# main.net
KiCad netlist of a schematic drawn in Altium Designer
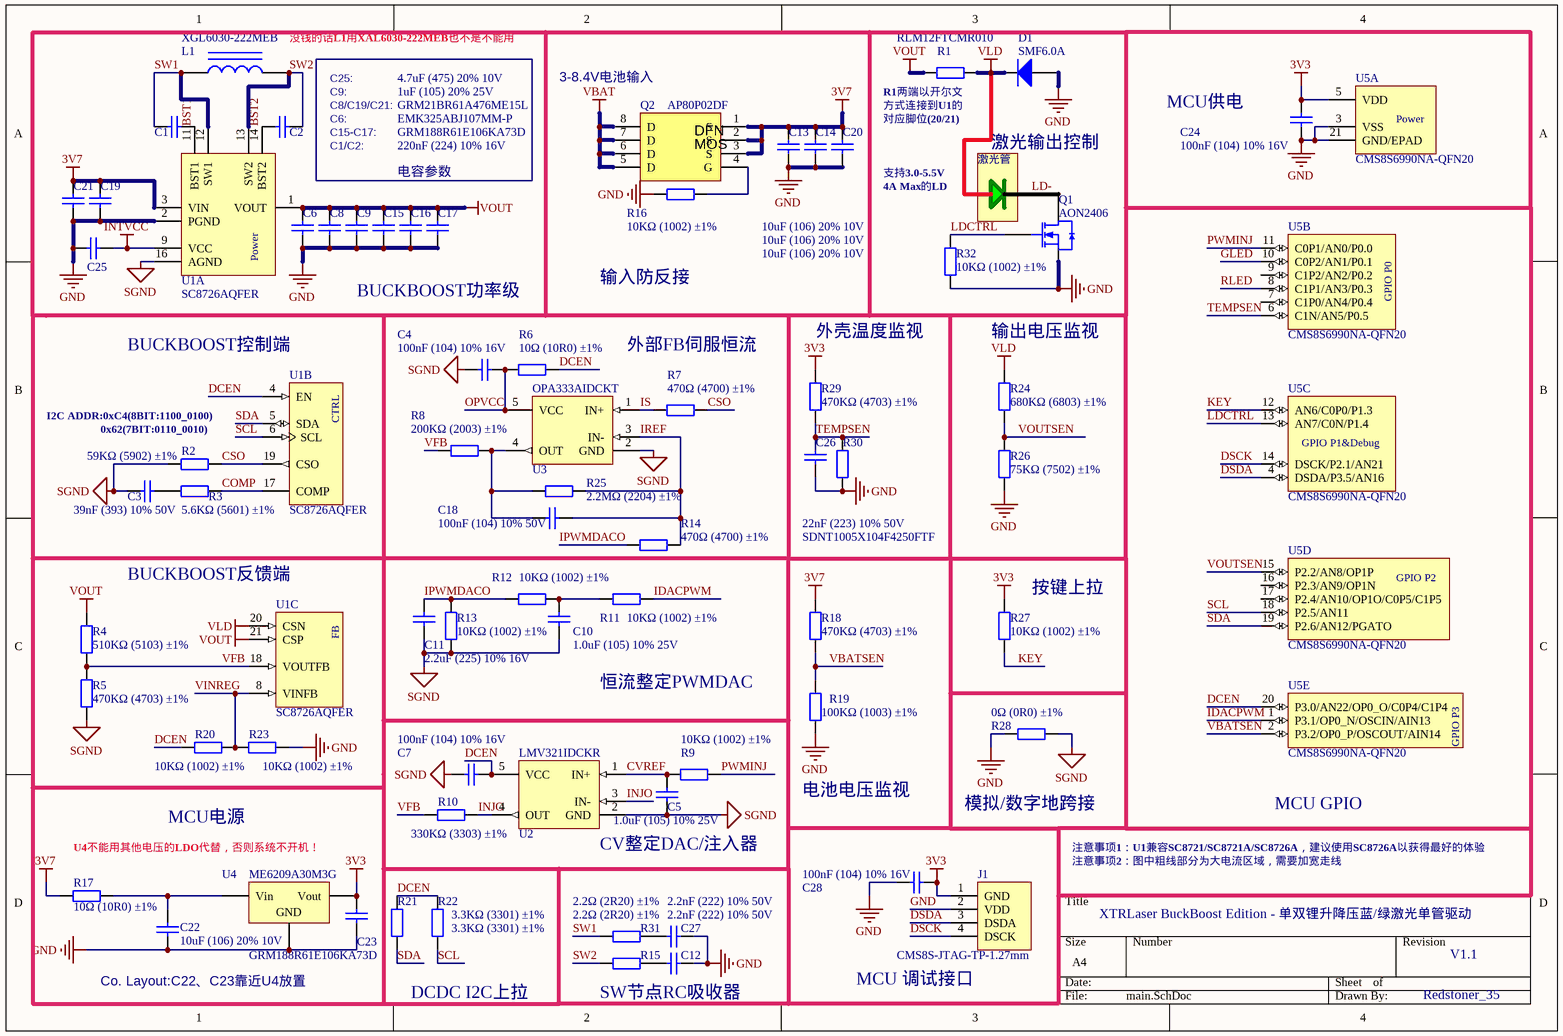
[diagram p0: main.SchDoc]

(export (version "E")
  (design (tool "Eeschema 10.0.6"))
  (components
    (comp (ref "C1")
      (value "220nF (224) 10% 16V")
      (footprint "0402_C")
      (description "贴片电容")
      (libsource (lib "Miscellaneous Devices LC") (part "0402 100nF (104) 10% 16V"))
    )
    (comp (ref "C2")
      (value "220nF (224) 10% 16V")
      (footprint "0402_C")
      (description "贴片电容")
      (libsource (lib "Miscellaneous Devices LC") (part "0402 100nF (104) 10% 16V"))
    )
    (comp (ref "C3")
      (value "39nF (393) 10% 50V")
      (footprint "0402_C")
      (description "贴片电容")
      (libsource (lib "Miscellaneous Devices LC") (part "0402 22nF (223) 10% 50V"))
    )
    (comp (ref "C4")
      (value "100nF (104) 10% 16V")
      (footprint "0402_C")
      (description "贴片电容")
      (libsource (lib "Miscellaneous Devices LC") (part "0402 100nF (104) 10% 16V"))
    )
    (comp (ref "C5")
      (value "1.0uF (105) 10% 25V")
      (footprint "0402_C")
      (description "贴片电容")
      (libsource (lib "Miscellaneous Devices LC") (part "0402 1.0uF (105) 10% 25V"))
    )
    (comp (ref "C6")
      (value "EMK325ABJ107MM-P")
      (footprint "1210C")
      (description "MLCC电容 10V 100uF±20% 16V X5R")
      (fields (field (name "PUBLISHER") "Altium Limited"))
      (libsource (lib "山猫的集成库20190318") (part "Cap"))
    )
    (comp (ref "C7")
      (value "100nF (104) 10% 16V")
      (footprint "0402_C")
      (description "贴片电容")
      (libsource (lib "Miscellaneous Devices LC") (part "0402 100nF (104) 10% 16V"))
    )
    (comp (ref "C8")
      (value "GRM21BR61A476ME15L")
      (footprint "0805_C")
      (description "贴片MLCC电容，47uF ±20% 10V X5R")
      (libsource (lib "Miscellaneous Devices LC") (part "0805 22uF (226) 20% 25V"))
    )
    (comp (ref "C9")
      (value "1uF (105) 20% 25V")
      (footprint "0402_C")
      (description "贴片电容")
      (libsource (lib "Miscellaneous Devices LC") (part "0402 4.7uF (475) 20% 10V"))
    )
    (comp (ref "C10")
      (value "1.0uF (105) 10% 25V")
      (footprint "0402_C")
      (description "贴片电容")
      (libsource (lib "Miscellaneous Devices LC") (part "0402 1.0uF (105) 10% 25V"))
    )
    (comp (ref "C11")
      (value "2.2uF (225) 10% 16V")
      (footprint "0402_C")
      (description "贴片电容")
      (libsource (lib "Miscellaneous Devices LC") (part "0402 2.2nF (222) 10% 50V"))
    )
    (comp (ref "C12")
      (value "2.2nF (222) 10% 50V")
      (footprint "0402_C")
      (description "贴片电容")
      (libsource (lib "Miscellaneous Devices LC") (part "0402 2.2nF (222) 10% 50V"))
    )
    (comp (ref "C13")
      (value "10uF (106) 20% 10V")
      (footprint "0402_C")
      (description "贴片电容")
      (libsource (lib "Miscellaneous Devices LC") (part "0402 10uF (106) 20% 6.3V"))
    )
    (comp (ref "C14")
      (value "10uF (106) 20% 10V")
      (footprint "0402_C")
      (description "贴片电容")
      (libsource (lib "Miscellaneous Devices LC") (part "0402 10uF (106) 20% 6.3V"))
    )
    (comp (ref "C15")
      (value "GRM188R61E106KA73D")
      (footprint "0603_C")
      (description "贴片MLCC电容 10uF±20% 10V X5R")
      (libsource (lib "Miscellaneous Devices LC") (part "0603 10uF (106) 10% 10V"))
    )
    (comp (ref "C16")
      (value "GRM188R61E106KA73D")
      (footprint "0603_C")
      (description "贴片MLCC电容 10uF±20% 10V X5R")
      (libsource (lib "Miscellaneous Devices LC") (part "0603 10uF (106) 10% 10V"))
    )
    (comp (ref "C17")
      (value "GRM188R61E106KA73D")
      (footprint "0603_C")
      (description "贴片MLCC电容 10uF±20% 10V X5R")
      (libsource (lib "Miscellaneous Devices LC") (part "0603 10uF (106) 10% 10V"))
    )
    (comp (ref "C18")
      (value "100nF (104) 10% 50V")
      (footprint "0402_C")
      (description "贴片电容")
      (libsource (lib "Miscellaneous Devices LC") (part "0402 10nF (103) 10% 50V"))
    )
    (comp (ref "C19")
      (value "GRM21BR61A476ME15L")
      (footprint "0805_C")
      (description "贴片MLCC电容，47uF ±20% 10V X5R")
      (libsource (lib "Miscellaneous Devices LC") (part "0805 22uF (226) 20% 25V"))
    )
    (comp (ref "C20")
      (value "10uF (106) 20% 10V")
      (footprint "0402_C")
      (description "贴片电容")
      (libsource (lib "Miscellaneous Devices LC") (part "0402 10uF (106) 20% 6.3V"))
    )
    (comp (ref "C21")
      (value "GRM21BR61A476ME15L")
      (footprint "0805_C")
      (description "贴片MLCC电容，47uF ±20% 10V X5R")
      (libsource (lib "Miscellaneous Devices LC") (part "0805 22uF (226) 20% 25V"))
    )
    (comp (ref "C22")
      (value "10uF (106) 20% 10V")
      (footprint "0402_C")
      (description "贴片电容")
      (libsource (lib "Miscellaneous Devices LC") (part "0402 10uF (106) 20% 6.3V"))
    )
    (comp (ref "C23")
      (value "GRM188R61E106KA73D")
      (footprint "0603_C")
      (description "贴片电容")
      (libsource (lib "Miscellaneous Devices LC") (part "0603 10uF (106) 10% 10V"))
    )
    (comp (ref "C24")
      (value "100nF (104) 10% 16V")
      (footprint "0402_C")
      (description "贴片电容")
      (libsource (lib "Miscellaneous Devices LC") (part "0402 100nF (104) 10% 16V"))
    )
    (comp (ref "C25")
      (value "4.7uF (475) 20% 10V")
      (footprint "0402_C")
      (description "贴片电容")
      (libsource (lib "Miscellaneous Devices LC") (part "0402 4.7uF (475) 20% 10V"))
    )
    (comp (ref "C26")
      (value "22nF (223) 10% 50V")
      (footprint "0402_C")
      (description "贴片电容")
      (libsource (lib "Miscellaneous Devices LC") (part "0402 10nF (103) 10% 50V"))
    )
    (comp (ref "C27")
      (value "2.2nF (222) 10% 50V")
      (footprint "0402_C")
      (description "贴片电容")
      (libsource (lib "Miscellaneous Devices LC") (part "0402 2.2nF (222) 10% 50V"))
    )
    (comp (ref "C28")
      (value "100nF (104) 10% 16V")
      (footprint "0402_C")
      (description "贴片电容")
      (libsource (lib "Miscellaneous Devices LC") (part "0402 100nF (104) 10% 16V"))
    )
    (comp (ref "D1")
      (value "SMF6.0A")
      (footprint "SOD-123")
      (description "TVS二极管 6V持续工作电压")
      (libsource (lib "Miscellaneous Devices LC") (part "SOD-123 B5819W  SL"))
    )
    (comp (ref "J1")
      (value "CMS8S-JTAG-TP-1.27mm")
      (footprint "CMS8S-JTAG-TP-2x2-P1.27")
      (description "面向CMS8S6990NA单片机的调试贴片触点，并不是元器件实物")
      (libsource (lib "custom") (part "CMS8S-JTAG-TP-1.27mm"))
    )
    (comp (ref "L1")
      (value "XGL6030-222MEB")
      (footprint "XAL6030-xxxME")
      (description "线艺XGL系列低损耗一体成型低内阻电感 2.2uH ±20% 8.7mΩ DCR 12A饱和电流")
      (fields (field (name "PUBLISHER") "Altium Limited"))
      (libsource (lib "Miscellaneous Devices") (part "Inductor Iron"))
    )
    (comp (ref "Q1")
      (value "AON2406")
      (footprint "PDFN-6_L2.0-W2.0-P0.65-BL-EP")
      (description "MOS(场效应管)")
      (libsource (lib "Miscellaneous Devices LC") (part "AO3400A N道沟 X0YV1T SOT-23"))
    )
    (comp (ref "Q2")
      (value "AP80P02DF")
      (footprint "DFN-8_L3.0-W3.0-P0.65-BL")
      (description "PDFN3x3 -20V 50A P沟道MOSFET 4.0mΩ @ -2.5V")
      (libsource (lib "custom") (part "SON/DFN5x6 MOS"))
    )
    (comp (ref "R1")
      (value "RLM12FTCMR010")
      (footprint "1206_R")
      (description "0.01Ω (R010) ±1% 1W 合金电流检测电阻")
      (libsource (lib "Miscellaneous Devices LC") (part "1206 0.1Ω (R100) 1%"))
    )
    (comp (ref "R2")
      (value "59KΩ (5902) ±1%")
      (footprint "0402_R")
      (description "贴片电阻")
      (libsource (lib "Miscellaneous Devices LC") (part "0402 56KΩ (5602) 1%"))
    )
    (comp (ref "R3")
      (value "5.6KΩ (5601) ±1%")
      (footprint "0402_R")
      (description "贴片电阻")
      (libsource (lib "Miscellaneous Devices LC") (part "0402 10KΩ (1002) 1%"))
    )
    (comp (ref "R4")
      (value "510KΩ (5103) ±1%")
      (footprint "0402_R")
      (description "贴片电阻")
      (libsource (lib "") (part "0402 100KΩ (1003) 1%_1"))
    )
    (comp (ref "R5")
      (value "470KΩ (4703) ±1%")
      (footprint "0402_R")
      (description "贴片电阻")
      (libsource (lib "") (part "0402 100KΩ (1003) 1%_1"))
    )
    (comp (ref "R6")
      (value "10Ω (10R0) ±1%")
      (footprint "0402_R")
      (description "贴片电阻")
      (libsource (lib "Miscellaneous Devices LC") (part "0402 10Ω (10R0) 1%"))
    )
    (comp (ref "R7")
      (value "470Ω (4700) ±1%")
      (footprint "0402_R")
      (description "贴片电阻")
      (libsource (lib "Miscellaneous Devices LC") (part "0402 470Ω (4700) 1%"))
    )
    (comp (ref "R8")
      (value "200KΩ (2003) ±1%")
      (footprint "0402_R")
      (description "贴片电阻")
      (libsource (lib "Miscellaneous Devices LC") (part "0402 100KΩ (1003) 1%"))
    )
    (comp (ref "R9")
      (value "10KΩ (1002) ±1%")
      (footprint "0402_R")
      (description "贴片电阻")
      (libsource (lib "Miscellaneous Devices LC") (part "0402 10KΩ (1002) 1%"))
    )
    (comp (ref "R10")
      (value "330KΩ (3303) ±1%")
      (footprint "0402_R")
      (description "贴片电阻")
      (libsource (lib "Miscellaneous Devices LC") (part "0402 330KΩ (3303) 1%"))
    )
    (comp (ref "R11")
      (value "10KΩ (1002) ±1%")
      (footprint "0402_R")
      (description "贴片电阻")
      (libsource (lib "Miscellaneous Devices LC") (part "0402 10KΩ (1002) 1%"))
    )
    (comp (ref "R12")
      (value "10KΩ (1002) ±1%")
      (footprint "0402_R")
      (description "贴片电阻")
      (libsource (lib "Miscellaneous Devices LC") (part "0402 10KΩ (1002) 1%"))
    )
    (comp (ref "R13")
      (value "10KΩ (1002) ±1%")
      (footprint "0402_R")
      (description "贴片电阻")
      (libsource (lib "") (part "0402 10KΩ (1002) 1%_2"))
    )
    (comp (ref "R14")
      (value "470Ω (4700) ±1%")
      (footprint "0402_R")
      (description "贴片电阻")
      (libsource (lib "") (part "0402 470Ω (4700) 1%_1"))
    )
    (comp (ref "R15")
      (value "2.2Ω (2R20) ±1%")
      (footprint "0402_R")
      (description "贴片电阻")
      (libsource (lib "") (part "0402 1Ω (1R00) 1%_1"))
    )
    (comp (ref "R16")
      (value "10KΩ (1002) ±1%")
      (footprint "0402_R")
      (description "贴片电阻")
      (libsource (lib "Miscellaneous Devices LC") (part "0402 10KΩ (1002) 1%"))
    )
    (comp (ref "R17")
      (value "10Ω (10R0) ±1%")
      (footprint "0402_R")
      (description "贴片电阻")
      (libsource (lib "Miscellaneous Devices LC") (part "0402 22Ω (22R0) 1%"))
    )
    (comp (ref "R18")
      (value "470KΩ (4703) ±1%")
      (footprint "0402_R")
      (description "贴片电阻")
      (libsource (lib "Miscellaneous Devices LC") (part "0402 470KΩ (4703) 1%"))
    )
    (comp (ref "R19")
      (value "100KΩ (1003) ±1%")
      (footprint "0402_R")
      (description "贴片电阻")
      (libsource (lib "") (part "0402 100KΩ (1003) 1%_1"))
    )
    (comp (ref "R20")
      (value "10KΩ (1002) ±1%")
      (footprint "0402_R")
      (description "贴片电阻")
      (libsource (lib "") (part "0402 10KΩ (1002) 1%_1"))
    )
    (comp (ref "R21")
      (value "3.3KΩ (3301) ±1%")
      (footprint "0402_R")
      (description "贴片电阻")
      (libsource (lib "Miscellaneous Devices LC") (part "0402 3.3KΩ (3301) 1%"))
    )
    (comp (ref "R22")
      (value "3.3KΩ (3301) ±1%")
      (footprint "0402_R")
      (description "贴片电阻")
      (libsource (lib "Miscellaneous Devices LC") (part "0402 3.3KΩ (3301) 1%"))
    )
    (comp (ref "R23")
      (value "10KΩ (1002) ±1%")
      (footprint "0402_R")
      (description "贴片电阻")
      (libsource (lib "") (part "0402 10KΩ (1002) 1%_1"))
    )
    (comp (ref "R24")
      (value "680KΩ (6803) ±1%")
      (footprint "0402_R")
      (description "贴片电阻")
      (libsource (lib "Miscellaneous Devices LC") (part "0402 470KΩ (4703) 1%"))
    )
    (comp (ref "R25")
      (value "2.2MΩ (2204) ±1%")
      (footprint "0402_R")
      (description "贴片电阻")
      (libsource (lib "Miscellaneous Devices LC") (part "0402 1MΩ (1004) 1%"))
    )
    (comp (ref "R26")
      (value "75KΩ (7502) ±1%")
      (footprint "0402_R")
      (description "贴片电阻")
      (libsource (lib "Miscellaneous Devices LC") (part "0402 68KΩ (6802) 1%"))
    )
    (comp (ref "R27")
      (value "10KΩ (1002) ±1%")
      (footprint "0402_R")
      (description "贴片电阻")
      (libsource (lib "") (part "0402 10KΩ (1002) 1%_2"))
    )
    (comp (ref "R28")
      (value "0Ω (0R0) ±1%")
      (footprint "0402_R")
      (description "贴片电阻")
      (libsource (lib "Miscellaneous Devices LC") (part "0402 0Ω (0R0) 1%"))
    )
    (comp (ref "R29")
      (value "470KΩ (4703) ±1%")
      (footprint "0402_R")
      (description "贴片电阻")
      (libsource (lib "Miscellaneous Devices LC") (part "0402 470KΩ (4703) 1%"))
    )
    (comp (ref "R30")
      (value "SDNT1005X104F4250FTF")
      (footprint "0402_R")
      (description "贴片热敏电阻0402 B4250 100K ±1%")
      (libsource (lib "Miscellaneous Devices LC") (part "0402 200KΩ (2003) 1%"))
    )
    (comp (ref "R31")
      (value "2.2Ω (2R20) ±1%")
      (footprint "0402_R")
      (description "贴片电阻")
      (libsource (lib "Miscellaneous Devices LC") (part "0402 1Ω (1R00) 1%"))
    )
    (comp (ref "R32")
      (value "10KΩ (1002) ±1%")
      (footprint "0402_R")
      (description "贴片电阻")
      (libsource (lib "") (part "0402 10KΩ (1002) 1%_2"))
    )
    (comp (ref "U1")
      (value "SC8726AQFER")
      (footprint "VQFN-21(4x4x0.75)")
      (description "同步单片集成式双向四开关单芯片集成升降压转换器，内置MOSFET，2.7-22V输入范围，2.4-22V输出范围，支持I2C控制")
      (libsource (lib "custom") (part "SC8721QFER"))
    )
    (comp (ref "U2")
      (value "LMV321IDCKR")
      (footprint "SC70-5")
      (description "CMOS超小型运算放大器，SC70-5")
      (libsource (lib "custom") (part "LMV321IDCKR"))
    )
    (comp (ref "U3")
      (value "OPA333AIDCKT")
      (footprint "SC70-5")
      (description "CMOS超小型0漂移运算放大器，SC70-5封装，350KHz GBW")
      (libsource (lib "custom") (part "LMV321IDCKR"))
    )
    (comp (ref "U4")
      (value "ME6209A30M3G")
      (footprint "SOT-23-3L")
      (description "低压差线性稳压(LDO)，输入耐压18V 输出3V 300mA最大电流 SOT23-3封装")
      (libsource (lib "Miscellaneous Devices LC") (part "SOT-23 XC6206P332MR"))
    )
    (comp (ref "U5")
      (value "CMS8S6990NA-QFN20")
      (footprint "QFN40P300X300X800_HS-21N")
      (description "增强型闪存1T 8051单片机，16KB Flash 256+1K XRAM")
      (libsource (lib "custom") (part "CM8S6990NA-QFN20"))
    )
  )
  (nets
    (net (code "1") (name "/BST1") (class "Default")
      (node (ref "C1") (pin "2") (pinfunction "2_2") (pintype "passive"))
      (node (ref "U1") (pin "11") (pinfunction "BST1_11") (pintype "power_in"))
    )
    (net (code "2") (name "/BST2") (class "Default")
      (node (ref "C2") (pin "1") (pinfunction "1_1") (pintype "passive"))
      (node (ref "U1") (pin "14") (pinfunction "BST2_14") (pintype "power_in"))
    )
    (net (code "3") (name "/COMP") (class "Default")
      (node (ref "R3") (pin "2") (pinfunction "2_2") (pintype "passive"))
      (node (ref "U1") (pin "17") (pinfunction "COMP_17") (pintype "passive"))
    )
    (net (code "4") (name "/CSO") (class "Default")
      (node (ref "R2") (pin "2") (pinfunction "2_2") (pintype "passive"))
      (node (ref "R7") (pin "2") (pinfunction "2_2") (pintype "passive"))
      (node (ref "U1") (pin "19") (pinfunction "CSO_19") (pintype "output"))
    )
    (net (code "5") (name "/CVREF") (class "Default")
      (node (ref "C5") (pin "2") (pinfunction "2_2") (pintype "passive"))
      (node (ref "R9") (pin "1") (pinfunction "1_1") (pintype "passive"))
      (node (ref "U2") (pin "1") (pinfunction "IN+_1") (pintype "input"))
    )
    (net (code "6") (name "/DCEN") (class "Default")
      (node (ref "C7") (pin "2") (pinfunction "2_2") (pintype "passive"))
      (node (ref "R20") (pin "2") (pinfunction "2_2") (pintype "passive"))
      (node (ref "R21") (pin "1") (pinfunction "1_1") (pintype "passive"))
      (node (ref "R22") (pin "1") (pinfunction "1_1") (pintype "passive"))
      (node (ref "R6") (pin "2") (pinfunction "2_2") (pintype "passive"))
      (node (ref "U1") (pin "4") (pinfunction "EN_4") (pintype "input"))
      (node (ref "U2") (pin "5") (pinfunction "VCC_5") (pintype "power_in"))
      (node (ref "U5") (pin "20") (pinfunction "P3.0/AN22/OP0_O/C0P4/C1P4_20") (pintype "bidirectional"))
    )
    (net (code "7") (name "/DSCK") (class "Default")
      (node (ref "J1") (pin "4") (pinfunction "DSCK_4") (pintype "passive"))
      (node (ref "U5") (pin "14") (pinfunction "DSCK/P2.1/AN21_14") (pintype "bidirectional"))
    )
    (net (code "8") (name "/DSDA") (class "Default")
      (node (ref "J1") (pin "3") (pinfunction "DSDA_3") (pintype "passive"))
      (node (ref "U5") (pin "4") (pinfunction "DSDA/P3.5/AN16_4") (pintype "bidirectional"))
    )
    (net (code "9") (name "/GLED") (class "Default")
      (node (ref "U5") (pin "10") (pinfunction "C0P2/AN1/P0.1_10") (pintype "bidirectional"))
    )
    (net (code "10") (name "/IDACPWM") (class "Default")
      (node (ref "R11") (pin "2") (pinfunction "2_2") (pintype "passive"))
      (node (ref "U5") (pin "1") (pinfunction "P3.1/OP0_N/OSCIN/AIN13_1") (pintype "bidirectional"))
    )
    (net (code "11") (name "/INJO") (class "Default")
      (node (ref "R10") (pin "2") (pinfunction "2_2") (pintype "passive"))
      (node (ref "U2") (pin "3") (pinfunction "IN-_3") (pintype "input"))
      (node (ref "U2") (pin "4") (pinfunction "OUT_4") (pintype "output"))
    )
    (net (code "12") (name "/IPWMDACO") (class "Default")
      (node (ref "C11") (pin "2") (pinfunction "2_2") (pintype "passive"))
      (node (ref "R12") (pin "1") (pinfunction "1_1") (pintype "passive"))
      (node (ref "R13") (pin "2") (pinfunction "2_2") (pintype "passive"))
      (node (ref "R14") (pin "2") (pinfunction "2_2") (pintype "passive"))
    )
    (net (code "13") (name "/IREF") (class "Default")
      (node (ref "C18") (pin "1") (pinfunction "1_1") (pintype "passive"))
      (node (ref "R14") (pin "1") (pinfunction "1_1") (pintype "passive"))
      (node (ref "R25") (pin "1") (pinfunction "1_1") (pintype "passive"))
      (node (ref "U3") (pin "3") (pinfunction "IN-_3") (pintype "input"))
    )
    (net (code "14") (name "/IS") (class "Default")
      (node (ref "R7") (pin "1") (pinfunction "1_1") (pintype "passive"))
      (node (ref "U3") (pin "1") (pinfunction "IN+_1") (pintype "input"))
    )
    (net (code "15") (name "/KEY") (class "Default")
      (node (ref "R27") (pin "1") (pinfunction "1_1") (pintype "passive"))
      (node (ref "U5") (pin "12") (pinfunction "AN6/C0P0/P1.3_12") (pintype "bidirectional"))
    )
    (net (code "16") (name "/LD-") (class "Default")
      (node (ref "Q1") (pin "3") (pinfunction "D_3") (pintype "passive"))
    )
    (net (code "17") (name "/LDCTRL") (class "Default")
      (node (ref "Q1") (pin "1") (pinfunction "G_1") (pintype "passive"))
      (node (ref "R32") (pin "2") (pinfunction "2_2") (pintype "passive"))
      (node (ref "U5") (pin "13") (pinfunction "AN7/C0N/P1.4_13") (pintype "bidirectional"))
    )
    (net (code "18") (name "/OPVCC") (class "Default")
      (node (ref "C4") (pin "2") (pinfunction "2_2") (pintype "passive"))
      (node (ref "R6") (pin "1") (pinfunction "1_1") (pintype "passive"))
      (node (ref "U3") (pin "5") (pinfunction "VCC_5") (pintype "power_in"))
    )
    (net (code "19") (name "/PWMINJ") (class "Default")
      (node (ref "R9") (pin "2") (pinfunction "2_2") (pintype "passive"))
      (node (ref "U5") (pin "11") (pinfunction "C0P1/AN0/P0.0_11") (pintype "bidirectional"))
    )
    (net (code "20") (name "/RLED") (class "Default")
      (node (ref "U5") (pin "8") (pinfunction "C1P1/AN3/P0.3_8") (pintype "bidirectional"))
    )
    (net (code "21") (name "/SCL") (class "Default")
      (node (ref "R22") (pin "2") (pinfunction "2_2") (pintype "passive"))
      (node (ref "U1") (pin "6") (pinfunction "SCL_6") (pintype "input"))
      (node (ref "U5") (pin "18") (pinfunction "P2.5/AN11_18") (pintype "bidirectional"))
    )
    (net (code "22") (name "/SDA") (class "Default")
      (node (ref "R21") (pin "2") (pinfunction "2_2") (pintype "passive"))
      (node (ref "U1") (pin "5") (pinfunction "SDA_5") (pintype "bidirectional"))
      (node (ref "U5") (pin "19") (pinfunction "P2.6/AN12/PGATO_19") (pintype "bidirectional"))
    )
    (net (code "23") (name "/SW1") (class "Default")
      (node (ref "C1") (pin "1") (pinfunction "1_1") (pintype "passive"))
      (node (ref "L1") (pin "1") (pinfunction "1_1") (pintype "passive"))
      (node (ref "R31") (pin "2") (pinfunction "2_2") (pintype "passive"))
      (node (ref "U1") (pin "12") (pinfunction "SW1_12") (pintype "power_in"))
    )
    (net (code "24") (name "/SW2") (class "Default")
      (node (ref "C2") (pin "2") (pinfunction "2_2") (pintype "passive"))
      (node (ref "L1") (pin "2") (pinfunction "2_2") (pintype "passive"))
      (node (ref "R15") (pin "1") (pinfunction "1_1") (pintype "passive"))
      (node (ref "U1") (pin "13") (pinfunction "SW2_13") (pintype "power_in"))
    )
    (net (code "25") (name "/TEMPSEN") (class "Default")
      (node (ref "C26") (pin "2") (pinfunction "2_2") (pintype "passive"))
      (node (ref "R29") (pin "1") (pinfunction "1_1") (pintype "passive"))
      (node (ref "R30") (pin "2") (pinfunction "2_2") (pintype "passive"))
      (node (ref "U5") (pin "6") (pinfunction "C1N/AN5/P0.5_6") (pintype "bidirectional"))
    )
    (net (code "26") (name "/VBATSEN") (class "Default")
      (node (ref "R18") (pin "1") (pinfunction "1_1") (pintype "passive"))
      (node (ref "R19") (pin "2") (pinfunction "2_2") (pintype "passive"))
      (node (ref "U5") (pin "2") (pinfunction "P3.2/OP0_P/OSCOUT/AIN14_2") (pintype "bidirectional"))
    )
    (net (code "27") (name "/VFB") (class "Default")
      (node (ref "R10") (pin "1") (pinfunction "1_1") (pintype "passive"))
      (node (ref "R4") (pin "1") (pinfunction "1_1") (pintype "passive"))
      (node (ref "R5") (pin "2") (pinfunction "2_2") (pintype "passive"))
      (node (ref "R8") (pin "1") (pinfunction "1_1") (pintype "passive"))
      (node (ref "U1") (pin "18") (pinfunction "VOUTFB_18") (pintype "input"))
    )
    (net (code "28") (name "/VINREG") (class "Default")
      (node (ref "R20") (pin "1") (pinfunction "1_1") (pintype "passive"))
      (node (ref "R23") (pin "2") (pinfunction "2_2") (pintype "passive"))
      (node (ref "U1") (pin "8") (pinfunction "VINFB_8") (pintype "input"))
    )
    (net (code "29") (name "/VOUTSEN") (class "Default")
      (node (ref "R24") (pin "1") (pinfunction "1_1") (pintype "passive"))
      (node (ref "R26") (pin "2") (pinfunction "2_2") (pintype "passive"))
      (node (ref "U5") (pin "15") (pinfunction "P2.2/AN8/OP1P_15") (pintype "bidirectional"))
    )
    (net (code "30") (name "3V3") (class "Default")
      (node (ref "C23") (pin "2") (pinfunction "2_2") (pintype "passive"))
      (node (ref "C24") (pin "2") (pinfunction "2_2") (pintype "passive"))
      (node (ref "C28") (pin "1") (pinfunction "1_1") (pintype "passive"))
      (node (ref "J1") (pin "1") (pinfunction "GND_1") (pintype "passive"))
      (node (ref "R27") (pin "2") (pinfunction "2_2") (pintype "passive"))
      (node (ref "R29") (pin "2") (pinfunction "2_2") (pintype "passive"))
      (node (ref "U4") (pin "2") (pinfunction "Vout_2") (pintype "passive"))
      (node (ref "U5") (pin "5") (pinfunction "VDD_5") (pintype "power_in"))
    )
    (net (code "31") (name "3V7") (class "Default")
      (node (ref "C13") (pin "2") (pinfunction "2_2") (pintype "passive"))
      (node (ref "C14") (pin "2") (pinfunction "2_2") (pintype "passive"))
      (node (ref "C19") (pin "2") (pinfunction "2_2") (pintype "passive"))
      (node (ref "C20") (pin "2") (pinfunction "2_2") (pintype "passive"))
      (node (ref "C21") (pin "2") (pinfunction "2_2") (pintype "passive"))
      (node (ref "Q2") (pin "1") (pinfunction "S_1") (pintype "passive"))
      (node (ref "Q2") (pin "2") (pinfunction "S_2") (pintype "passive"))
      (node (ref "Q2") (pin "3") (pinfunction "S_3") (pintype "passive"))
      (node (ref "R17") (pin "1") (pinfunction "1_1") (pintype "passive"))
      (node (ref "R18") (pin "2") (pinfunction "2_2") (pintype "passive"))
      (node (ref "U1") (pin "3") (pinfunction "VIN_3") (pintype "power_in"))
    )
    (net (code "32") (name "GND") (class "Default")
      (node (ref "C12") (pin "2") (pinfunction "2_2") (pintype "passive"))
      (node (ref "C13") (pin "1") (pinfunction "1_1") (pintype "passive"))
      (node (ref "C14") (pin "1") (pinfunction "1_1") (pintype "passive"))
      (node (ref "C15") (pin "1") (pinfunction "1_1") (pintype "passive"))
      (node (ref "C16") (pin "1") (pinfunction "1_1") (pintype "passive"))
      (node (ref "C17") (pin "1") (pinfunction "1_1") (pintype "passive"))
      (node (ref "C19") (pin "1") (pinfunction "1_1") (pintype "passive"))
      (node (ref "C20") (pin "1") (pinfunction "1_1") (pintype "passive"))
      (node (ref "C21") (pin "1") (pinfunction "1_1") (pintype "passive"))
      (node (ref "C22") (pin "1") (pinfunction "1_1") (pintype "passive"))
      (node (ref "C23") (pin "1") (pinfunction "1_1") (pintype "passive"))
      (node (ref "C24") (pin "1") (pinfunction "1_1") (pintype "passive"))
      (node (ref "C25") (pin "1") (pinfunction "1_1") (pintype "passive"))
      (node (ref "C26") (pin "1") (pinfunction "1_1") (pintype "passive"))
      (node (ref "C27") (pin "1") (pinfunction "1_1") (pintype "passive"))
      (node (ref "C28") (pin "2") (pinfunction "2_2") (pintype "passive"))
      (node (ref "C6") (pin "1") (pinfunction "1_1") (pintype "passive"))
      (node (ref "C8") (pin "1") (pinfunction "1_1") (pintype "passive"))
      (node (ref "C9") (pin "2") (pinfunction "2_2") (pintype "passive"))
      (node (ref "D1") (pin "1") (pinfunction "A_1") (pintype "passive"))
      (node (ref "J1") (pin "2") (pinfunction "VDD_2") (pintype "passive"))
      (node (ref "Q1") (pin "2") (pinfunction "S_2") (pintype "passive"))
      (node (ref "R16") (pin "1") (pinfunction "1_1") (pintype "passive"))
      (node (ref "R19") (pin "1") (pinfunction "1_1") (pintype "passive"))
      (node (ref "R23") (pin "1") (pinfunction "1_1") (pintype "passive"))
      (node (ref "R26") (pin "1") (pinfunction "1_1") (pintype "passive"))
      (node (ref "R28") (pin "2") (pinfunction "2_2") (pintype "passive"))
      (node (ref "R30") (pin "1") (pinfunction "1_1") (pintype "passive"))
      (node (ref "R32") (pin "1") (pinfunction "1_1") (pintype "passive"))
      (node (ref "U1") (pin "2") (pinfunction "PGND_2") (pintype "power_in"))
      (node (ref "U4") (pin "1") (pinfunction "GND_1") (pintype "passive"))
      (node (ref "U5") (pin "21") (pinfunction "GND/EPAD_21") (pintype "power_in"))
      (node (ref "U5") (pin "3") (pinfunction "VSS_3") (pintype "power_in"))
    )
    (net (code "33") (name "INTVCC") (class "Default")
      (node (ref "C25") (pin "2") (pinfunction "2_2") (pintype "passive"))
      (node (ref "U1") (pin "9") (pinfunction "VCC_9") (pintype "power_in"))
    )
    (net (code "34") (name "Net-(C3-Pad2)") (class "Default")
      (node (ref "C3") (pin "2") (pinfunction "2_2") (pintype "passive"))
      (node (ref "R3") (pin "1") (pinfunction "1_1") (pintype "passive"))
    )
    (net (code "35") (name "Net-(C10-Pad1)") (class "Default")
      (node (ref "C10") (pin "1") (pinfunction "1_1") (pintype "passive"))
      (node (ref "R11") (pin "1") (pinfunction "1_1") (pintype "passive"))
      (node (ref "R12") (pin "2") (pinfunction "2_2") (pintype "passive"))
    )
    (net (code "36") (name "Net-(C12-Pad1)") (class "Default")
      (node (ref "C12") (pin "1") (pinfunction "1_1") (pintype "passive"))
      (node (ref "R15") (pin "2") (pinfunction "2_2") (pintype "passive"))
    )
    (net (code "37") (name "Net-(C27-Pad2)") (class "Default")
      (node (ref "C27") (pin "2") (pinfunction "2_2") (pintype "passive"))
      (node (ref "R31") (pin "1") (pinfunction "1_1") (pintype "passive"))
    )
    (net (code "38") (name "Net-(Q2-G)") (class "Default")
      (node (ref "Q2") (pin "4") (pinfunction "G_4") (pintype "passive"))
      (node (ref "R16") (pin "2") (pinfunction "2_2") (pintype "passive"))
    )
    (net (code "39") (name "Net-(U3-OUT)") (class "Default")
      (node (ref "C18") (pin "2") (pinfunction "2_2") (pintype "passive"))
      (node (ref "R25") (pin "2") (pinfunction "2_2") (pintype "passive"))
      (node (ref "R8") (pin "2") (pinfunction "2_2") (pintype "passive"))
      (node (ref "U3") (pin "4") (pinfunction "OUT_4") (pintype "output"))
    )
    (net (code "40") (name "Net-(U4-Vin)") (class "Default")
      (node (ref "C22") (pin "2") (pinfunction "2_2") (pintype "passive"))
      (node (ref "R17") (pin "2") (pinfunction "2_2") (pintype "passive"))
      (node (ref "U4") (pin "3") (pinfunction "Vin_3") (pintype "passive"))
    )
    (net (code "41") (name "SGND") (class "Default")
      (node (ref "C10") (pin "2") (pinfunction "2_2") (pintype "passive"))
      (node (ref "C11") (pin "1") (pinfunction "1_1") (pintype "passive"))
      (node (ref "C3") (pin "1") (pinfunction "1_1") (pintype "passive"))
      (node (ref "C4") (pin "1") (pinfunction "1_1") (pintype "passive"))
      (node (ref "C5") (pin "1") (pinfunction "1_1") (pintype "passive"))
      (node (ref "C7") (pin "1") (pinfunction "1_1") (pintype "passive"))
      (node (ref "R13") (pin "1") (pinfunction "1_1") (pintype "passive"))
      (node (ref "R2") (pin "1") (pinfunction "1_1") (pintype "passive"))
      (node (ref "R28") (pin "1") (pinfunction "1_1") (pintype "passive"))
      (node (ref "R5") (pin "1") (pinfunction "1_1") (pintype "passive"))
      (node (ref "U1") (pin "16") (pinfunction "AGND_16") (pintype "power_in"))
      (node (ref "U2") (pin "2") (pinfunction "GND_2") (pintype "power_in"))
      (node (ref "U3") (pin "2") (pinfunction "GND_2") (pintype "power_in"))
    )
    (net (code "42") (name "VBAT") (class "Default")
      (node (ref "Q2") (pin "5") (pinfunction "D_5") (pintype "passive"))
      (node (ref "Q2") (pin "6") (pinfunction "D_6") (pintype "passive"))
      (node (ref "Q2") (pin "7") (pinfunction "D_7") (pintype "passive"))
      (node (ref "Q2") (pin "8") (pinfunction "D_8") (pintype "passive"))
    )
    (net (code "43") (name "VLD") (class "Default")
      (node (ref "D1") (pin "2") (pinfunction "K_2") (pintype "passive"))
      (node (ref "R1") (pin "2") (pinfunction "2_2") (pintype "passive"))
      (node (ref "R24") (pin "2") (pinfunction "2_2") (pintype "passive"))
      (node (ref "U1") (pin "20") (pinfunction "CSN_20") (pintype "input"))
    )
    (net (code "44") (name "VOUT") (class "Default")
      (node (ref "C15") (pin "2") (pinfunction "2_2") (pintype "passive"))
      (node (ref "C16") (pin "2") (pinfunction "2_2") (pintype "passive"))
      (node (ref "C17") (pin "2") (pinfunction "2_2") (pintype "passive"))
      (node (ref "C6") (pin "2") (pinfunction "2_2") (pintype "passive"))
      (node (ref "C8") (pin "2") (pinfunction "2_2") (pintype "passive"))
      (node (ref "C9") (pin "1") (pinfunction "1_1") (pintype "passive"))
      (node (ref "R1") (pin "1") (pinfunction "1_1") (pintype "passive"))
      (node (ref "R4") (pin "2") (pinfunction "2_2") (pintype "passive"))
      (node (ref "U1") (pin "1") (pinfunction "VOUT_1") (pintype "power_in"))
      (node (ref "U1") (pin "21") (pinfunction "CSP_21") (pintype "input"))
    )
    (net (code "45") (name "unconnected-(U5B-C1P0{slash}AN4{slash}P0.4-Pad7)") (class "Default")
      (node (ref "U5") (pin "7") (pinfunction "C1P0/AN4/P0.4_7") (pintype "bidirectional"))
    )
    (net (code "46") (name "unconnected-(U5B-C1P2{slash}AN2{slash}P0.2-Pad9)") (class "Default")
      (node (ref "U5") (pin "9") (pinfunction "C1P2/AN2/P0.2_9") (pintype "bidirectional"))
    )
    (net (code "47") (name "unconnected-(U5D-P2.3{slash}AN9{slash}OP1N-Pad16)") (class "Default")
      (node (ref "U5") (pin "16") (pinfunction "P2.3/AN9/OP1N_16") (pintype "bidirectional"))
    )
    (net (code "48") (name "unconnected-(U5D-P2.4{slash}AN10{slash}OP1O{slash}C0P5{slash}C1P5-Pad17)") (class "Default")
      (node (ref "U5") (pin "17") (pinfunction "P2.4/AN10/OP1O/C0P5/C1P5_17") (pintype "bidirectional"))
    )
  )
)
